# PCMCIA_1.net
KiCad netlist of a schematic drawn in Altium Designer
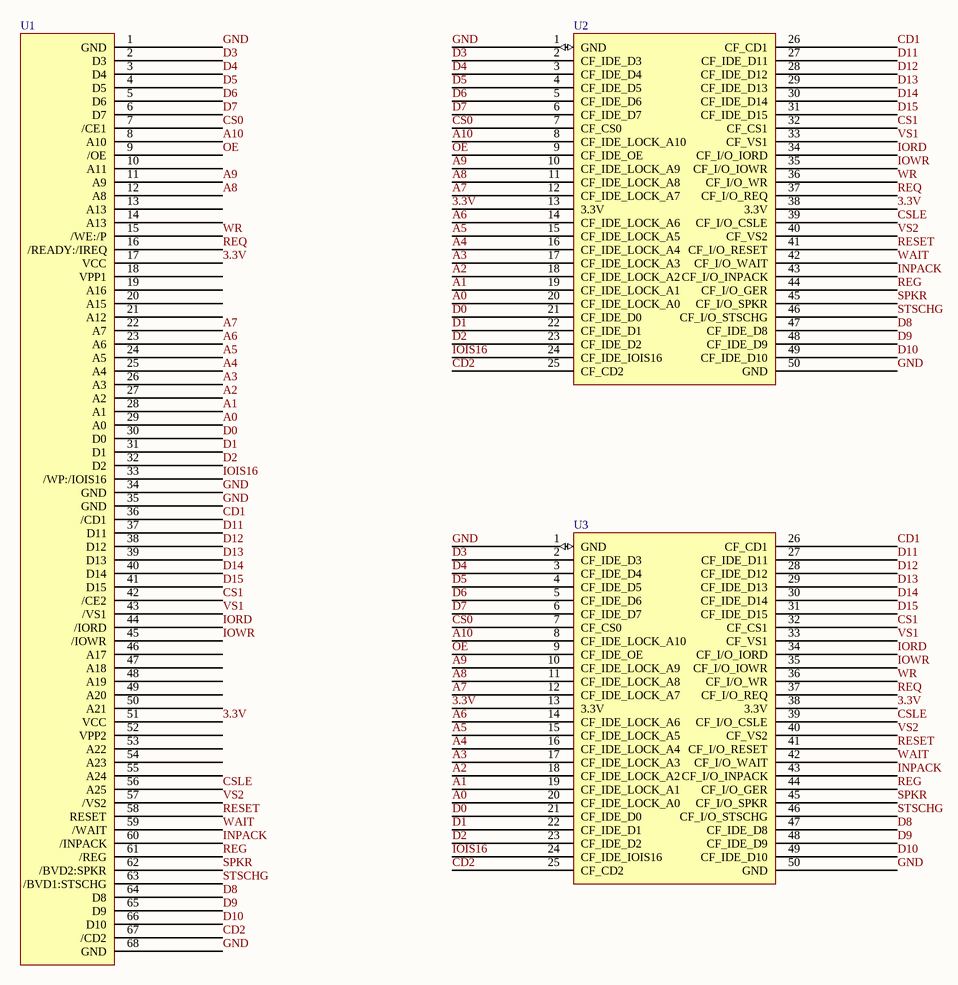
[diagram p0: PCMCIA_1.SchDoc]

(export (version "E")
  (design (tool "Eeschema 10.0.6"))
  (components
    (comp (ref "U1") (value "~") (footprint "PCMCIA_68pin_F") (libsource (lib "AD - 副本") (part "Ultrasonic")))
    (comp (ref "U2") (value "~") (footprint "DIP40_600MIL") (libsource (lib "AD - 副本") (part "AT89S52_1")))
    (comp (ref "U3") (value "~") (footprint "DIP40_600MIL") (libsource (lib "AD - 副本") (part "AT89S52_1")))
  )
  (nets
    (net (code "1") (name "/3.3V") (class "Default")
      (node (ref "U1") (pin "17") (pinfunction "VCC_17") (pintype "passive"))
      (node (ref "U1") (pin "51") (pinfunction "VCC_51") (pintype "passive"))
      (node (ref "U2") (pin "13") (pinfunction "3.3V_13") (pintype "passive"))
      (node (ref "U2") (pin "38") (pinfunction "3.3V_38") (pintype "passive"))
      (node (ref "U3") (pin "13") (pinfunction "3.3V_13") (pintype "passive"))
      (node (ref "U3") (pin "38") (pinfunction "3.3V_38") (pintype "passive"))
    )
    (net (code "2") (name "/A0") (class "Default")
      (node (ref "U1") (pin "29") (pinfunction "A0_29") (pintype "passive"))
      (node (ref "U2") (pin "20") (pinfunction "CF_IDE_LOCK_A0_20") (pintype "passive"))
      (node (ref "U3") (pin "20") (pinfunction "CF_IDE_LOCK_A0_20") (pintype "passive"))
    )
    (net (code "3") (name "/A1") (class "Default")
      (node (ref "U1") (pin "28") (pinfunction "A1_28") (pintype "passive"))
      (node (ref "U2") (pin "19") (pinfunction "CF_IDE_LOCK_A1_19") (pintype "passive"))
      (node (ref "U3") (pin "19") (pinfunction "CF_IDE_LOCK_A1_19") (pintype "passive"))
    )
    (net (code "4") (name "/A2") (class "Default")
      (node (ref "U1") (pin "27") (pinfunction "A2_27") (pintype "passive"))
      (node (ref "U2") (pin "18") (pinfunction "CF_IDE_LOCK_A2_18") (pintype "passive"))
      (node (ref "U3") (pin "18") (pinfunction "CF_IDE_LOCK_A2_18") (pintype "passive"))
    )
    (net (code "5") (name "/A3") (class "Default")
      (node (ref "U1") (pin "26") (pinfunction "A3_26") (pintype "passive"))
      (node (ref "U2") (pin "17") (pinfunction "CF_IDE_LOCK_A3_17") (pintype "passive"))
      (node (ref "U3") (pin "17") (pinfunction "CF_IDE_LOCK_A3_17") (pintype "passive"))
    )
    (net (code "6") (name "/A4") (class "Default")
      (node (ref "U1") (pin "25") (pinfunction "A4_25") (pintype "passive"))
      (node (ref "U2") (pin "16") (pinfunction "CF_IDE_LOCK_A4_16") (pintype "passive"))
      (node (ref "U3") (pin "16") (pinfunction "CF_IDE_LOCK_A4_16") (pintype "passive"))
    )
    (net (code "7") (name "/A5") (class "Default")
      (node (ref "U1") (pin "24") (pinfunction "A5_24") (pintype "passive"))
      (node (ref "U2") (pin "15") (pinfunction "CF_IDE_LOCK_A5_15") (pintype "passive"))
      (node (ref "U3") (pin "15") (pinfunction "CF_IDE_LOCK_A5_15") (pintype "passive"))
    )
    (net (code "8") (name "/A6") (class "Default")
      (node (ref "U1") (pin "23") (pinfunction "A6_23") (pintype "passive"))
      (node (ref "U2") (pin "14") (pinfunction "CF_IDE_LOCK_A6_14") (pintype "passive"))
      (node (ref "U3") (pin "14") (pinfunction "CF_IDE_LOCK_A6_14") (pintype "passive"))
    )
    (net (code "9") (name "/A7") (class "Default")
      (node (ref "U1") (pin "22") (pinfunction "A7_22") (pintype "passive"))
      (node (ref "U2") (pin "12") (pinfunction "CF_IDE_LOCK_A7_12") (pintype "passive"))
      (node (ref "U3") (pin "12") (pinfunction "CF_IDE_LOCK_A7_12") (pintype "passive"))
    )
    (net (code "10") (name "/A8") (class "Default")
      (node (ref "U1") (pin "12") (pinfunction "A8_12") (pintype "passive"))
      (node (ref "U2") (pin "11") (pinfunction "CF_IDE_LOCK_A8_11") (pintype "passive"))
      (node (ref "U3") (pin "11") (pinfunction "CF_IDE_LOCK_A8_11") (pintype "passive"))
    )
    (net (code "11") (name "/A9") (class "Default")
      (node (ref "U1") (pin "11") (pinfunction "A9_11") (pintype "passive"))
      (node (ref "U2") (pin "10") (pinfunction "CF_IDE_LOCK_A9_10") (pintype "passive"))
      (node (ref "U3") (pin "10") (pinfunction "CF_IDE_LOCK_A9_10") (pintype "passive"))
    )
    (net (code "12") (name "/A10") (class "Default")
      (node (ref "U1") (pin "8") (pinfunction "A10_8") (pintype "passive"))
      (node (ref "U2") (pin "8") (pinfunction "CF_IDE_LOCK_A10_8") (pintype "passive"))
      (node (ref "U3") (pin "8") (pinfunction "CF_IDE_LOCK_A10_8") (pintype "passive"))
    )
    (net (code "13") (name "/CD1") (class "Default")
      (node (ref "U1") (pin "36") (pinfunction "/CD1_36") (pintype "passive"))
      (node (ref "U2") (pin "26") (pinfunction "CF_CD1_26") (pintype "passive"))
      (node (ref "U3") (pin "26") (pinfunction "CF_CD1_26") (pintype "passive"))
    )
    (net (code "14") (name "/CD2") (class "Default")
      (node (ref "U1") (pin "67") (pinfunction "/CD2_67") (pintype "passive"))
      (node (ref "U2") (pin "25") (pinfunction "CF_CD2_25") (pintype "passive"))
      (node (ref "U3") (pin "25") (pinfunction "CF_CD2_25") (pintype "passive"))
    )
    (net (code "15") (name "/CS0") (class "Default")
      (node (ref "U1") (pin "7") (pinfunction "/CE1_7") (pintype "passive"))
      (node (ref "U2") (pin "7") (pinfunction "CF_CS0_7") (pintype "passive"))
      (node (ref "U3") (pin "7") (pinfunction "CF_CS0_7") (pintype "passive"))
    )
    (net (code "16") (name "/CS1") (class "Default")
      (node (ref "U1") (pin "42") (pinfunction "/CE2_42") (pintype "passive"))
      (node (ref "U2") (pin "32") (pinfunction "CF_CS1_32") (pintype "passive"))
      (node (ref "U3") (pin "32") (pinfunction "CF_CS1_32") (pintype "passive"))
    )
    (net (code "17") (name "/CSLE") (class "Default")
      (node (ref "U1") (pin "56") (pinfunction "A25_56") (pintype "passive"))
      (node (ref "U2") (pin "39") (pinfunction "CF_I/O_CSLE_39") (pintype "passive"))
      (node (ref "U3") (pin "39") (pinfunction "CF_I/O_CSLE_39") (pintype "passive"))
    )
    (net (code "18") (name "/D0") (class "Default")
      (node (ref "U1") (pin "30") (pinfunction "D0_30") (pintype "passive"))
      (node (ref "U2") (pin "21") (pinfunction "CF_IDE_D0_21") (pintype "passive"))
      (node (ref "U3") (pin "21") (pinfunction "CF_IDE_D0_21") (pintype "passive"))
    )
    (net (code "19") (name "/D1") (class "Default")
      (node (ref "U1") (pin "31") (pinfunction "D1_31") (pintype "passive"))
      (node (ref "U2") (pin "22") (pinfunction "CF_IDE_D1_22") (pintype "passive"))
      (node (ref "U3") (pin "22") (pinfunction "CF_IDE_D1_22") (pintype "passive"))
    )
    (net (code "20") (name "/D2") (class "Default")
      (node (ref "U1") (pin "32") (pinfunction "D2_32") (pintype "passive"))
      (node (ref "U2") (pin "23") (pinfunction "CF_IDE_D2_23") (pintype "passive"))
      (node (ref "U3") (pin "23") (pinfunction "CF_IDE_D2_23") (pintype "passive"))
    )
    (net (code "21") (name "/D3") (class "Default")
      (node (ref "U1") (pin "2") (pinfunction "D3_2") (pintype "passive"))
      (node (ref "U2") (pin "2") (pinfunction "CF_IDE_D3_2") (pintype "passive"))
      (node (ref "U3") (pin "2") (pinfunction "CF_IDE_D3_2") (pintype "passive"))
    )
    (net (code "22") (name "/D4") (class "Default")
      (node (ref "U1") (pin "3") (pinfunction "D4_3") (pintype "passive"))
      (node (ref "U2") (pin "3") (pinfunction "CF_IDE_D4_3") (pintype "passive"))
      (node (ref "U3") (pin "3") (pinfunction "CF_IDE_D4_3") (pintype "passive"))
    )
    (net (code "23") (name "/D5") (class "Default")
      (node (ref "U1") (pin "4") (pinfunction "D5_4") (pintype "passive"))
      (node (ref "U2") (pin "4") (pinfunction "CF_IDE_D5_4") (pintype "passive"))
      (node (ref "U3") (pin "4") (pinfunction "CF_IDE_D5_4") (pintype "passive"))
    )
    (net (code "24") (name "/D6") (class "Default")
      (node (ref "U1") (pin "5") (pinfunction "D6_5") (pintype "passive"))
      (node (ref "U2") (pin "5") (pinfunction "CF_IDE_D6_5") (pintype "passive"))
      (node (ref "U3") (pin "5") (pinfunction "CF_IDE_D6_5") (pintype "passive"))
    )
    (net (code "25") (name "/D7") (class "Default")
      (node (ref "U1") (pin "6") (pinfunction "D7_6") (pintype "passive"))
      (node (ref "U2") (pin "6") (pinfunction "CF_IDE_D7_6") (pintype "passive"))
      (node (ref "U3") (pin "6") (pinfunction "CF_IDE_D7_6") (pintype "passive"))
    )
    (net (code "26") (name "/D8") (class "Default")
      (node (ref "U1") (pin "64") (pinfunction "D8_64") (pintype "passive"))
      (node (ref "U2") (pin "47") (pinfunction "CF_IDE_D8_47") (pintype "passive"))
      (node (ref "U3") (pin "47") (pinfunction "CF_IDE_D8_47") (pintype "passive"))
    )
    (net (code "27") (name "/D9") (class "Default")
      (node (ref "U1") (pin "65") (pinfunction "D9_65") (pintype "passive"))
      (node (ref "U2") (pin "48") (pinfunction "CF_IDE_D9_48") (pintype "passive"))
      (node (ref "U3") (pin "48") (pinfunction "CF_IDE_D9_48") (pintype "passive"))
    )
    (net (code "28") (name "/D10") (class "Default")
      (node (ref "U1") (pin "66") (pinfunction "D10_66") (pintype "passive"))
      (node (ref "U2") (pin "49") (pinfunction "CF_IDE_D10_49") (pintype "passive"))
      (node (ref "U3") (pin "49") (pinfunction "CF_IDE_D10_49") (pintype "passive"))
    )
    (net (code "29") (name "/D11") (class "Default")
      (node (ref "U1") (pin "37") (pinfunction "D11_37") (pintype "passive"))
      (node (ref "U2") (pin "27") (pinfunction "CF_IDE_D11_27") (pintype "passive"))
      (node (ref "U3") (pin "27") (pinfunction "CF_IDE_D11_27") (pintype "passive"))
    )
    (net (code "30") (name "/D12") (class "Default")
      (node (ref "U1") (pin "38") (pinfunction "D12_38") (pintype "passive"))
      (node (ref "U2") (pin "28") (pinfunction "CF_IDE_D12_28") (pintype "passive"))
      (node (ref "U3") (pin "28") (pinfunction "CF_IDE_D12_28") (pintype "passive"))
    )
    (net (code "31") (name "/D13") (class "Default")
      (node (ref "U1") (pin "39") (pinfunction "D13_39") (pintype "passive"))
      (node (ref "U2") (pin "29") (pinfunction "CF_IDE_D13_29") (pintype "passive"))
      (node (ref "U3") (pin "29") (pinfunction "CF_IDE_D13_29") (pintype "passive"))
    )
    (net (code "32") (name "/D14") (class "Default")
      (node (ref "U1") (pin "40") (pinfunction "D14_40") (pintype "passive"))
      (node (ref "U2") (pin "30") (pinfunction "CF_IDE_D14_30") (pintype "passive"))
      (node (ref "U3") (pin "30") (pinfunction "CF_IDE_D14_30") (pintype "passive"))
    )
    (net (code "33") (name "/D15") (class "Default")
      (node (ref "U1") (pin "41") (pinfunction "D15_41") (pintype "passive"))
      (node (ref "U2") (pin "31") (pinfunction "CF_IDE_D15_31") (pintype "passive"))
      (node (ref "U3") (pin "31") (pinfunction "CF_IDE_D15_31") (pintype "passive"))
    )
    (net (code "34") (name "/GND") (class "Default")
      (node (ref "U1") (pin "1") (pinfunction "GND_1") (pintype "passive"))
      (node (ref "U1") (pin "34") (pinfunction "GND_34") (pintype "passive"))
      (node (ref "U1") (pin "35") (pinfunction "GND_35") (pintype "passive"))
      (node (ref "U1") (pin "68") (pinfunction "GND_68") (pintype "passive"))
      (node (ref "U2") (pin "1") (pinfunction "GND_1") (pintype "bidirectional"))
      (node (ref "U2") (pin "50") (pinfunction "GND_50") (pintype "passive"))
      (node (ref "U3") (pin "1") (pinfunction "GND_1") (pintype "bidirectional"))
      (node (ref "U3") (pin "50") (pinfunction "GND_50") (pintype "passive"))
    )
    (net (code "35") (name "/INPACK") (class "Default")
      (node (ref "U1") (pin "60") (pinfunction "/INPACK_60") (pintype "passive"))
      (node (ref "U2") (pin "43") (pinfunction "CF_I/O_INPACK_43") (pintype "passive"))
      (node (ref "U3") (pin "43") (pinfunction "CF_I/O_INPACK_43") (pintype "passive"))
    )
    (net (code "36") (name "/IOIS16") (class "Default")
      (node (ref "U1") (pin "33") (pinfunction "/WP:/IOIS16_33") (pintype "passive"))
      (node (ref "U2") (pin "24") (pinfunction "CF_IDE_IOIS16_24") (pintype "passive"))
      (node (ref "U3") (pin "24") (pinfunction "CF_IDE_IOIS16_24") (pintype "passive"))
    )
    (net (code "37") (name "/IORD") (class "Default")
      (node (ref "U1") (pin "44") (pinfunction "/IORD_44") (pintype "passive"))
      (node (ref "U2") (pin "34") (pinfunction "CF_I/O_IORD_34") (pintype "passive"))
      (node (ref "U3") (pin "34") (pinfunction "CF_I/O_IORD_34") (pintype "passive"))
    )
    (net (code "38") (name "/IOWR") (class "Default")
      (node (ref "U1") (pin "45") (pinfunction "/IOWR_45") (pintype "passive"))
      (node (ref "U2") (pin "35") (pinfunction "CF_I/O_IOWR_35") (pintype "passive"))
      (node (ref "U3") (pin "35") (pinfunction "CF_I/O_IOWR_35") (pintype "passive"))
    )
    (net (code "39") (name "/OE") (class "Default")
      (node (ref "U1") (pin "9") (pinfunction "/OE_9") (pintype "passive"))
      (node (ref "U2") (pin "9") (pinfunction "CF_IDE_OE_9") (pintype "passive"))
      (node (ref "U3") (pin "9") (pinfunction "CF_IDE_OE_9") (pintype "passive"))
    )
    (net (code "40") (name "/REG") (class "Default")
      (node (ref "U1") (pin "61") (pinfunction "/REG_61") (pintype "passive"))
      (node (ref "U2") (pin "44") (pinfunction "CF_I/O_GER_44") (pintype "passive"))
      (node (ref "U3") (pin "44") (pinfunction "CF_I/O_GER_44") (pintype "passive"))
    )
    (net (code "41") (name "/REQ") (class "Default")
      (node (ref "U1") (pin "16") (pinfunction "/READY:/IREQ_16") (pintype "passive"))
      (node (ref "U2") (pin "37") (pinfunction "CF_I/O_REQ_37") (pintype "passive"))
      (node (ref "U3") (pin "37") (pinfunction "CF_I/O_REQ_37") (pintype "passive"))
    )
    (net (code "42") (name "/RESET") (class "Default")
      (node (ref "U1") (pin "58") (pinfunction "RESET_58") (pintype "passive"))
      (node (ref "U2") (pin "41") (pinfunction "CF_I/O_RESET_41") (pintype "passive"))
      (node (ref "U3") (pin "41") (pinfunction "CF_I/O_RESET_41") (pintype "passive"))
    )
    (net (code "43") (name "/SPKR") (class "Default")
      (node (ref "U1") (pin "62") (pinfunction "/BVD2:SPKR_62") (pintype "passive"))
      (node (ref "U2") (pin "45") (pinfunction "CF_I/O_SPKR_45") (pintype "passive"))
      (node (ref "U3") (pin "45") (pinfunction "CF_I/O_SPKR_45") (pintype "passive"))
    )
    (net (code "44") (name "/STSCHG") (class "Default")
      (node (ref "U1") (pin "63") (pinfunction "/BVD1:STSCHG_63") (pintype "passive"))
      (node (ref "U2") (pin "46") (pinfunction "CF_I/O_STSCHG_46") (pintype "passive"))
      (node (ref "U3") (pin "46") (pinfunction "CF_I/O_STSCHG_46") (pintype "passive"))
    )
    (net (code "45") (name "/VS1") (class "Default")
      (node (ref "U1") (pin "43") (pinfunction "/VS1_43") (pintype "passive"))
      (node (ref "U2") (pin "33") (pinfunction "CF_VS1_33") (pintype "passive"))
      (node (ref "U3") (pin "33") (pinfunction "CF_VS1_33") (pintype "passive"))
    )
    (net (code "46") (name "/VS2") (class "Default")
      (node (ref "U1") (pin "57") (pinfunction "/VS2_57") (pintype "passive"))
      (node (ref "U2") (pin "40") (pinfunction "CF_VS2_40") (pintype "passive"))
      (node (ref "U3") (pin "40") (pinfunction "CF_VS2_40") (pintype "passive"))
    )
    (net (code "47") (name "/WAIT") (class "Default")
      (node (ref "U1") (pin "59") (pinfunction "/WAIT_59") (pintype "passive"))
      (node (ref "U2") (pin "42") (pinfunction "CF_I/O_WAIT_42") (pintype "passive"))
      (node (ref "U3") (pin "42") (pinfunction "CF_I/O_WAIT_42") (pintype "passive"))
    )
    (net (code "48") (name "/WR") (class "Default")
      (node (ref "U1") (pin "15") (pinfunction "/WE:/P_15") (pintype "passive"))
      (node (ref "U2") (pin "36") (pinfunction "CF_I/O_WR_36") (pintype "passive"))
      (node (ref "U3") (pin "36") (pinfunction "CF_I/O_WR_36") (pintype "passive"))
    )
    (net (code "49") (name "unconnected-(U1-A11-Pad10)") (class "Default")
      (node (ref "U1") (pin "10") (pinfunction "A11_10") (pintype "passive"))
    )
    (net (code "50") (name "unconnected-(U1-A12-Pad21)") (class "Default")
      (node (ref "U1") (pin "21") (pinfunction "A12_21") (pintype "passive"))
    )
    (net (code "51") (name "unconnected-(U1-A13-Pad13)") (class "Default")
      (node (ref "U1") (pin "13") (pinfunction "A13_13") (pintype "passive"))
    )
    (net (code "52") (name "unconnected-(U1-A13-Pad14)") (class "Default")
      (node (ref "U1") (pin "14") (pinfunction "A13_14") (pintype "passive"))
    )
    (net (code "53") (name "unconnected-(U1-A15-Pad20)") (class "Default")
      (node (ref "U1") (pin "20") (pinfunction "A15_20") (pintype "passive"))
    )
    (net (code "54") (name "unconnected-(U1-A16-Pad19)") (class "Default")
      (node (ref "U1") (pin "19") (pinfunction "A16_19") (pintype "passive"))
    )
    (net (code "55") (name "unconnected-(U1-A17-Pad46)") (class "Default")
      (node (ref "U1") (pin "46") (pinfunction "A17_46") (pintype "passive"))
    )
    (net (code "56") (name "unconnected-(U1-A18-Pad47)") (class "Default")
      (node (ref "U1") (pin "47") (pinfunction "A18_47") (pintype "passive"))
    )
    (net (code "57") (name "unconnected-(U1-A19-Pad48)") (class "Default")
      (node (ref "U1") (pin "48") (pinfunction "A19_48") (pintype "passive"))
    )
    (net (code "58") (name "unconnected-(U1-A20-Pad49)") (class "Default")
      (node (ref "U1") (pin "49") (pinfunction "A20_49") (pintype "passive"))
    )
    (net (code "59") (name "unconnected-(U1-A21-Pad50)") (class "Default")
      (node (ref "U1") (pin "50") (pinfunction "A21_50") (pintype "passive"))
    )
    (net (code "60") (name "unconnected-(U1-A22-Pad53)") (class "Default")
      (node (ref "U1") (pin "53") (pinfunction "A22_53") (pintype "passive"))
    )
    (net (code "61") (name "unconnected-(U1-A23-Pad54)") (class "Default")
      (node (ref "U1") (pin "54") (pinfunction "A23_54") (pintype "passive"))
    )
    (net (code "62") (name "unconnected-(U1-A24-Pad55)") (class "Default")
      (node (ref "U1") (pin "55") (pinfunction "A24_55") (pintype "passive"))
    )
    (net (code "63") (name "unconnected-(U1-VPP1-Pad18)") (class "Default")
      (node (ref "U1") (pin "18") (pinfunction "VPP1_18") (pintype "passive"))
    )
    (net (code "64") (name "unconnected-(U1-VPP2-Pad52)") (class "Default")
      (node (ref "U1") (pin "52") (pinfunction "VPP2_52") (pintype "passive"))
    )
  )
)
